# untitled.net
KiCad netlist of a schematic drawn in EAGLE
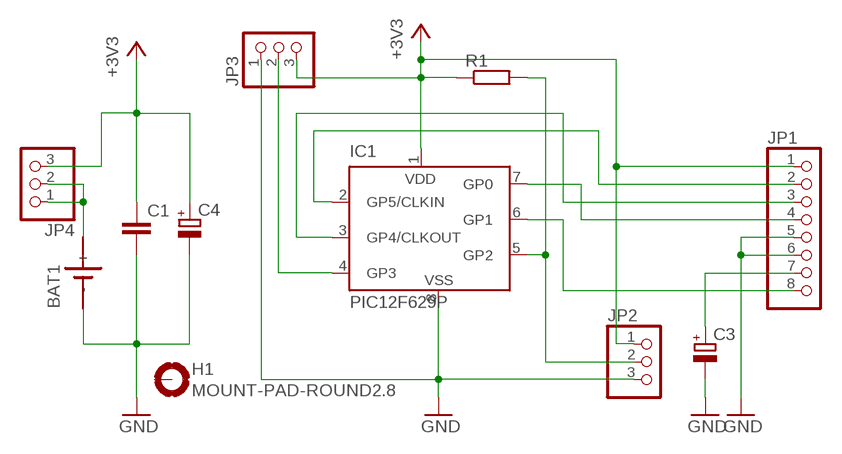
[diagram p0: schematic, sheet 1]

(export (version "E")
  (design (tool "Eeschema 10.0.6"))
  (components
    (comp (ref "BAT1")
      (value "SN2032")
      (footprint "eagle-import:SN2032")
      (libsource (lib "eagle-import") (part "SN2032"))
    )
    (comp (ref "C1")
      (value "C-EU025-025X050")
      (footprint "eagle-import:C025-025X050")
      (libsource (lib "eagle-import") (part "C-EU025-025X050"))
    )
    (comp (ref "C3")
      (value "CPOL-EUTT2D5L")
      (footprint "eagle-import:TT2D5L")
      (libsource (lib "eagle-import") (part "CPOL-EUTT2D5L"))
    )
    (comp (ref "C4")
      (value "CPOL-EUTT2D5L")
      (footprint "eagle-import:TT2D5L")
      (libsource (lib "eagle-import") (part "CPOL-EUTT2D5L"))
    )
    (comp (ref "H1")
      (value "MOUNT-PAD-ROUND2.8")
      (footprint "eagle-import:2,8-PAD")
      (libsource (lib "eagle-import") (part "MOUNT-PAD-ROUND2.8"))
    )
    (comp (ref "IC1")
      (value "PIC12F629P")
      (footprint "eagle-import:DIL8")
      (fields (field (name "MF") "MICROCHIP") (field (name "MPN") "PIC12F629-I/P"))
      (libsource (lib "eagle-import") (part "PIC12F6P29"))
    )
    (comp (ref "JP1")
      (value "PINHD-1X8")
      (footprint "eagle-import:1X08")
      (libsource (lib "eagle-import") (part "PINHD-1X8"))
    )
    (comp (ref "JP2")
      (value "PINHD-1X3")
      (footprint "eagle-import:1X03")
      (libsource (lib "eagle-import") (part "PINHD-1X3"))
    )
    (comp (ref "JP3")
      (value "PINHD-1X3")
      (footprint "eagle-import:1X03")
      (libsource (lib "eagle-import") (part "PINHD-1X3"))
    )
    (comp (ref "JP4")
      (value "PINHD-1X3")
      (footprint "eagle-import:1X03")
      (libsource (lib "eagle-import") (part "PINHD-1X3"))
    )
    (comp (ref "R1")
      (value "R-EU_0204/2V")
      (footprint "eagle-import:0204V")
      (libsource (lib "eagle-import") (part "R-EU_0204/2V"))
    )
  )
  (nets
    (net (code "1") (name "+3V3") (class "Default")
      (node (ref "C1") (pin "1") (pinfunction "1_1") (pintype "passive"))
      (node (ref "C4") (pin "+") (pinfunction "+_+") (pintype "passive"))
      (node (ref "IC1") (pin "1") (pinfunction "VDD_1") (pintype "power_in"))
      (node (ref "JP1") (pin "1") (pinfunction "1_1") (pintype "passive"))
      (node (ref "JP2") (pin "1") (pinfunction "1_1") (pintype "passive"))
      (node (ref "JP3") (pin "3") (pinfunction "3_3") (pintype "passive"))
      (node (ref "JP4") (pin "3") (pinfunction "3_3") (pintype "passive"))
      (node (ref "R1") (pin "1") (pinfunction "1_1") (pintype "passive"))
    )
    (net (code "2") (name "GND") (class "Default")
      (node (ref "BAT1") (pin "-") (pinfunction "-_-") (pintype "passive"))
      (node (ref "C1") (pin "2") (pinfunction "2_2") (pintype "passive"))
      (node (ref "C3") (pin "-") (pinfunction "-_-") (pintype "passive"))
      (node (ref "C4") (pin "-") (pinfunction "-_-") (pintype "passive"))
      (node (ref "IC1") (pin "8") (pinfunction "VSS_8") (pintype "power_in"))
      (node (ref "JP1") (pin "5") (pinfunction "5_5") (pintype "passive"))
      (node (ref "JP1") (pin "6") (pinfunction "6_6") (pintype "passive"))
      (node (ref "JP2") (pin "3") (pinfunction "3_3") (pintype "passive"))
      (node (ref "JP3") (pin "1") (pinfunction "1_1") (pintype "passive"))
    )
    (net (code "3") (name "Net-(BAT1-Pad+)") (class "Default")
      (node (ref "BAT1") (pin "+") (pinfunction "+_+") (pintype "passive"))
      (node (ref "JP4") (pin "1") (pinfunction "1_1") (pintype "passive"))
      (node (ref "JP4") (pin "2") (pinfunction "2_2") (pintype "passive"))
    )
    (net (code "4") (name "Net-(C3-Pad+)") (class "Default")
      (node (ref "C3") (pin "+") (pinfunction "+_+") (pintype "passive"))
      (node (ref "JP1") (pin "7") (pinfunction "7_7") (pintype "passive"))
    )
    (net (code "5") (name "Net-(IC1-GP0)") (class "Default")
      (node (ref "IC1") (pin "7") (pinfunction "GP0_7") (pintype "bidirectional"))
      (node (ref "JP1") (pin "4") (pinfunction "4_4") (pintype "passive"))
    )
    (net (code "6") (name "Net-(IC1-GP1)") (class "Default")
      (node (ref "IC1") (pin "6") (pinfunction "GP1_6") (pintype "bidirectional"))
      (node (ref "JP1") (pin "8") (pinfunction "8_8") (pintype "passive"))
    )
    (net (code "7") (name "Net-(IC1-GP2)") (class "Default")
      (node (ref "IC1") (pin "5") (pinfunction "GP2_5") (pintype "bidirectional"))
      (node (ref "JP2") (pin "2") (pinfunction "2_2") (pintype "passive"))
      (node (ref "R1") (pin "2") (pinfunction "2_2") (pintype "passive"))
    )
    (net (code "8") (name "Net-(IC1-GP3)") (class "Default")
      (node (ref "IC1") (pin "4") (pinfunction "GP3_4") (pintype "input"))
      (node (ref "JP3") (pin "2") (pinfunction "2_2") (pintype "passive"))
    )
    (net (code "9") (name "Net-(IC1-GP4{slash}CLKOUT)") (class "Default")
      (node (ref "IC1") (pin "3") (pinfunction "GP4/CLKOUT_3") (pintype "bidirectional"))
      (node (ref "JP1") (pin "3") (pinfunction "3_3") (pintype "passive"))
    )
    (net (code "10") (name "Net-(IC1-GP5{slash}CLKIN)") (class "Default")
      (node (ref "IC1") (pin "2") (pinfunction "GP5/CLKIN_2") (pintype "bidirectional"))
      (node (ref "JP1") (pin "2") (pinfunction "2_2") (pintype "passive"))
    )
    (net (code "11") (name "unconnected-(H1-MOUNT-PadB2,8)") (class "Default")
      (node (ref "H1") (pin "B2,8") (pinfunction "MOUNT_B2,8") (pintype "passive"))
    )
  )
)
